# Concentrator_and_Cell_Modem_Headers.net
KiCad netlist of a schematic drawn in Altium Designer
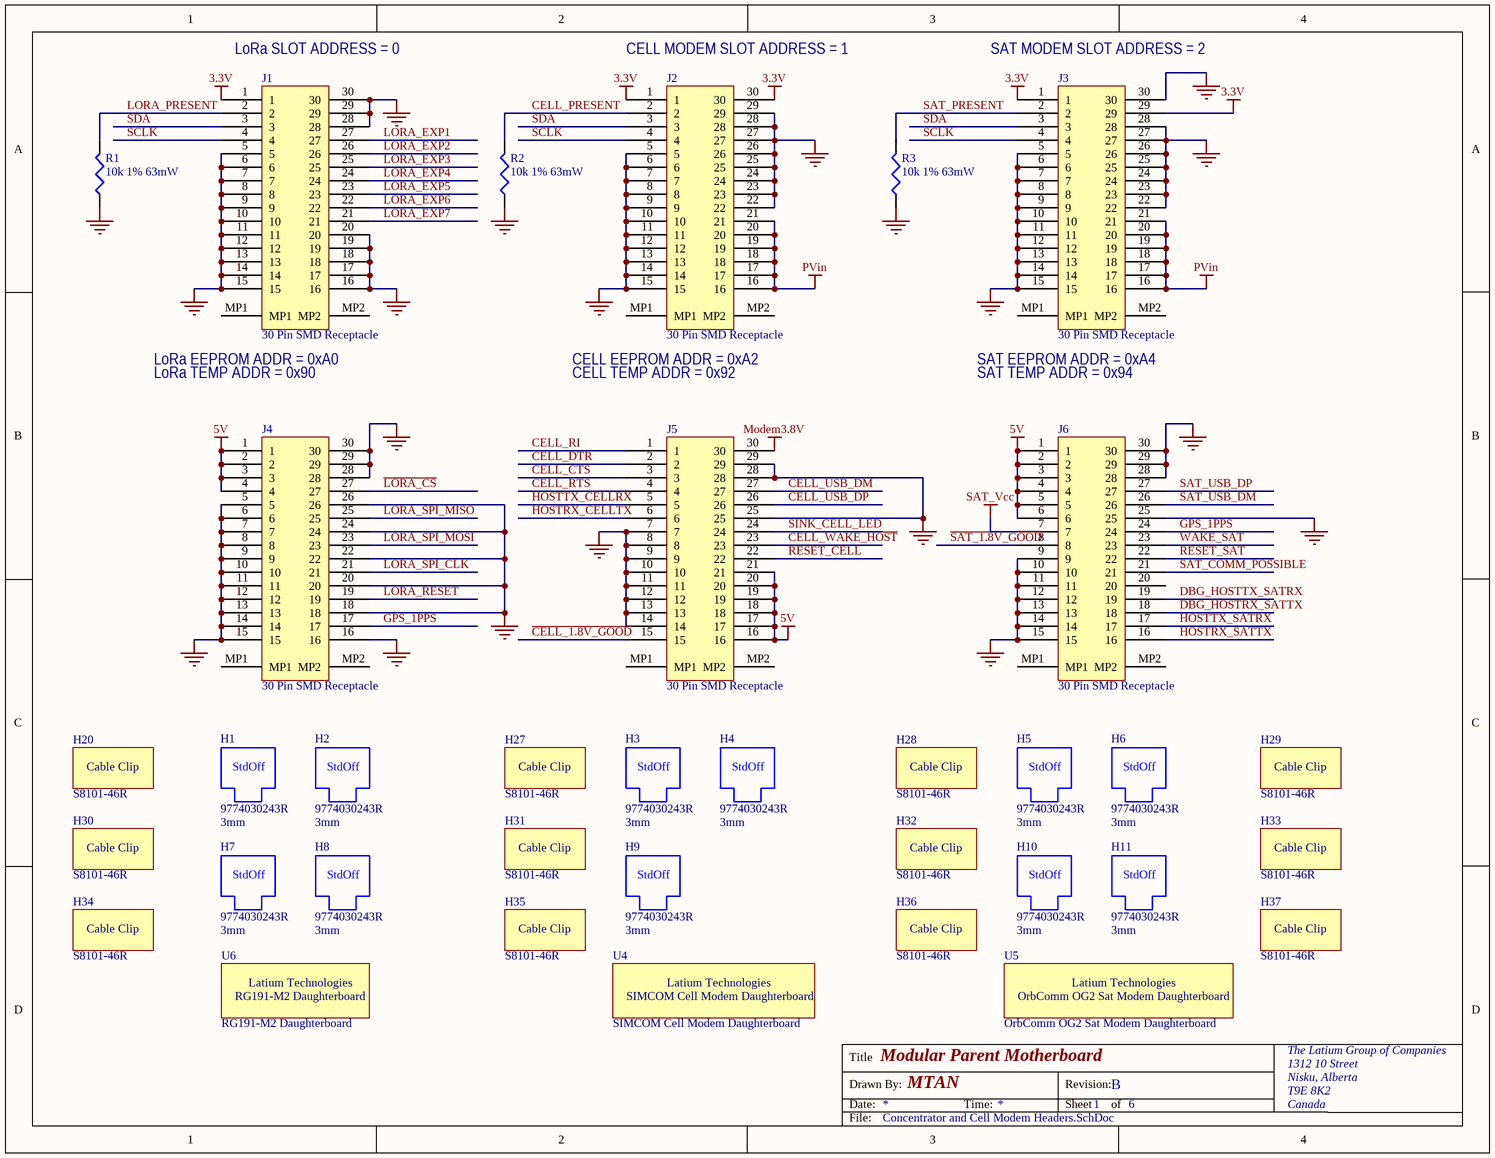
[diagram p0: Concentrator and Cell Modem Headers.SchDoc]

(export (version "E")
  (design (tool "Eeschema 10.0.6"))
  (components
    (comp (ref "H1")
      (value "9774030243R")
      (footprint "Wurth 9774030243R")
      (description "ROUND STANDOFF M2X0.4 STEEL 3MM")
      (fields (field (name "MANUFACTURER") "Wurth Electronics Inc") (field (name "HEIGHT") "3mm"))
      (libsource (lib "Latium Component Library") (part "SMD M3 Spacer"))
    )
    (comp (ref "H2")
      (value "9774030243R")
      (footprint "Wurth 9774030243R")
      (description "ROUND STANDOFF M2X0.4 STEEL 3MM")
      (fields (field (name "MANUFACTURER") "Wurth Electronics Inc") (field (name "HEIGHT") "3mm"))
      (libsource (lib "Latium Component Library") (part "SMD M3 Spacer"))
    )
    (comp (ref "H3")
      (value "9774030243R")
      (footprint "Wurth 9774030243R")
      (description "ROUND STANDOFF M2X0.4 STEEL 3MM")
      (fields (field (name "MANUFACTURER") "Wurth Electronics Inc") (field (name "HEIGHT") "3mm"))
      (libsource (lib "Latium Component Library") (part "SMD M3 Spacer"))
    )
    (comp (ref "H4")
      (value "9774030243R")
      (footprint "Wurth 9774030243R")
      (description "ROUND STANDOFF M2X0.4 STEEL 3MM")
      (fields (field (name "MANUFACTURER") "Wurth Electronics Inc") (field (name "HEIGHT") "3mm"))
      (libsource (lib "Latium Component Library") (part "SMD M3 Spacer"))
    )
    (comp (ref "H5")
      (value "9774030243R")
      (footprint "Wurth 9774030243R")
      (description "ROUND STANDOFF M2X0.4 STEEL 3MM")
      (fields (field (name "MANUFACTURER") "Wurth Electronics Inc") (field (name "HEIGHT") "3mm"))
      (libsource (lib "Latium Component Library") (part "SMD M3 Spacer"))
    )
    (comp (ref "H6")
      (value "9774030243R")
      (footprint "Wurth 9774030243R")
      (description "ROUND STANDOFF M2X0.4 STEEL 3MM")
      (fields (field (name "MANUFACTURER") "Wurth Electronics Inc") (field (name "HEIGHT") "3mm"))
      (libsource (lib "Latium Component Library") (part "SMD M3 Spacer"))
    )
    (comp (ref "H7")
      (value "9774030243R")
      (footprint "Wurth 9774030243R")
      (description "ROUND STANDOFF M2X0.4 STEEL 3MM")
      (fields (field (name "MANUFACTURER") "Wurth Electronics Inc") (field (name "HEIGHT") "3mm"))
      (libsource (lib "Latium Component Library") (part "SMD M3 Spacer"))
    )
    (comp (ref "H8")
      (value "9774030243R")
      (footprint "Wurth 9774030243R")
      (description "ROUND STANDOFF M2X0.4 STEEL 3MM")
      (fields (field (name "MANUFACTURER") "Wurth Electronics Inc") (field (name "HEIGHT") "3mm"))
      (libsource (lib "Latium Component Library") (part "SMD M3 Spacer"))
    )
    (comp (ref "H9")
      (value "9774030243R")
      (footprint "Wurth 9774030243R")
      (description "ROUND STANDOFF M2X0.4 STEEL 3MM")
      (fields (field (name "MANUFACTURER") "Wurth Electronics Inc") (field (name "HEIGHT") "3mm"))
      (libsource (lib "Latium Component Library") (part "SMD M3 Spacer"))
    )
    (comp (ref "H10")
      (value "9774030243R")
      (footprint "Wurth 9774030243R")
      (description "ROUND STANDOFF M2X0.4 STEEL 3MM")
      (fields (field (name "MANUFACTURER") "Wurth Electronics Inc") (field (name "HEIGHT") "3mm"))
      (libsource (lib "Latium Component Library") (part "SMD M3 Spacer"))
    )
    (comp (ref "H11")
      (value "9774030243R")
      (footprint "Wurth 9774030243R")
      (description "ROUND STANDOFF M2X0.4 STEEL 3MM")
      (fields (field (name "MANUFACTURER") "Wurth Electronics Inc") (field (name "HEIGHT") "3mm"))
      (libsource (lib "Latium Component Library") (part "SMD M3 Spacer"))
    )
    (comp (ref "H20")
      (value "S8101-46R")
      (footprint "Coax Cable Clip")
      (description "CBL CLIP C-TYPE SILVER SOLDER")
      (fields (field (name "MANUFACTURER") "Harwin Inc"))
      (libsource (lib "Latium Component Library") (part "Cable Clip"))
    )
    (comp (ref "H27")
      (value "S8101-46R")
      (footprint "Coax Cable Clip")
      (description "CBL CLIP C-TYPE SILVER SOLDER")
      (fields (field (name "MANUFACTURER") "Harwin Inc"))
      (libsource (lib "Latium Component Library") (part "Cable Clip"))
    )
    (comp (ref "H28")
      (value "S8101-46R")
      (footprint "Coax Cable Clip")
      (description "CBL CLIP C-TYPE SILVER SOLDER")
      (fields (field (name "MANUFACTURER") "Harwin Inc"))
      (libsource (lib "Latium Component Library") (part "Cable Clip"))
    )
    (comp (ref "H29")
      (value "S8101-46R")
      (footprint "Coax Cable Clip")
      (description "CBL CLIP C-TYPE SILVER SOLDER")
      (fields (field (name "MANUFACTURER") "Harwin Inc"))
      (libsource (lib "Latium Component Library") (part "Cable Clip"))
    )
    (comp (ref "H30")
      (value "S8101-46R")
      (footprint "Coax Cable Clip")
      (description "CBL CLIP C-TYPE SILVER SOLDER")
      (fields (field (name "MANUFACTURER") "Harwin Inc"))
      (libsource (lib "Latium Component Library") (part "Cable Clip"))
    )
    (comp (ref "H31")
      (value "S8101-46R")
      (footprint "Coax Cable Clip")
      (description "CBL CLIP C-TYPE SILVER SOLDER")
      (fields (field (name "MANUFACTURER") "Harwin Inc"))
      (libsource (lib "Latium Component Library") (part "Cable Clip"))
    )
    (comp (ref "H32")
      (value "S8101-46R")
      (footprint "Coax Cable Clip")
      (description "CBL CLIP C-TYPE SILVER SOLDER")
      (fields (field (name "MANUFACTURER") "Harwin Inc"))
      (libsource (lib "Latium Component Library") (part "Cable Clip"))
    )
    (comp (ref "H33")
      (value "S8101-46R")
      (footprint "Coax Cable Clip")
      (description "CBL CLIP C-TYPE SILVER SOLDER")
      (fields (field (name "MANUFACTURER") "Harwin Inc"))
      (libsource (lib "Latium Component Library") (part "Cable Clip"))
    )
    (comp (ref "H34")
      (value "S8101-46R")
      (footprint "Coax Cable Clip")
      (description "CBL CLIP C-TYPE SILVER SOLDER")
      (fields (field (name "MANUFACTURER") "Harwin Inc"))
      (libsource (lib "Latium Component Library") (part "Cable Clip"))
    )
    (comp (ref "H35")
      (value "S8101-46R")
      (footprint "Coax Cable Clip")
      (description "CBL CLIP C-TYPE SILVER SOLDER")
      (fields (field (name "MANUFACTURER") "Harwin Inc"))
      (libsource (lib "Latium Component Library") (part "Cable Clip"))
    )
    (comp (ref "H36")
      (value "S8101-46R")
      (footprint "Coax Cable Clip")
      (description "CBL CLIP C-TYPE SILVER SOLDER")
      (fields (field (name "MANUFACTURER") "Harwin Inc"))
      (libsource (lib "Latium Component Library") (part "Cable Clip"))
    )
    (comp (ref "H37")
      (value "S8101-46R")
      (footprint "Coax Cable Clip")
      (description "CBL CLIP C-TYPE SILVER SOLDER")
      (fields (field (name "MANUFACTURER") "Harwin Inc"))
      (libsource (lib "Latium Component Library") (part "Cable Clip"))
    )
    (comp (ref "J1")
      (value "30 Pin SMD Receptacle")
      (footprint "10132798-031100LF")
      (description "CONN RCPT 30POS SMD GOLD")
      (fields
        (field (name "MANUFACTURER") "Amphenol ICC (FCI)")
        (field (name "MANUFACTURER PART NUMBER") "10132798-031100LF")
      )
      (libsource (lib "Latium Component Library") (part "Amphenol 30 Pos BergStak Plug"))
    )
    (comp (ref "J2")
      (value "30 Pin SMD Receptacle")
      (footprint "10132798-031100LF")
      (description "CONN RCPT 30POS SMD GOLD")
      (fields
        (field (name "MANUFACTURER") "Amphenol ICC (FCI)")
        (field (name "MANUFACTURER PART NUMBER") "10132798-031100LF")
      )
      (libsource (lib "Latium Component Library") (part "Amphenol 30 Pos BergStak Plug"))
    )
    (comp (ref "J3")
      (value "30 Pin SMD Receptacle")
      (footprint "10132798-031100LF")
      (description "CONN RCPT 30POS SMD GOLD")
      (fields
        (field (name "MANUFACTURER") "Amphenol ICC (FCI)")
        (field (name "MANUFACTURER PART NUMBER") "10132798-031100LF")
      )
      (libsource (lib "Latium Component Library") (part "Amphenol 30 Pos BergStak Plug"))
    )
    (comp (ref "J4")
      (value "30 Pin SMD Receptacle")
      (footprint "10132798-031100LF")
      (description "CONN RCPT 30POS SMD GOLD")
      (fields
        (field (name "MANUFACTURER") "Amphenol ICC (FCI)")
        (field (name "MANUFACTURER PART NUMBER") "10132798-031100LF")
      )
      (libsource (lib "Latium Component Library") (part "Amphenol 30 Pos BergStak Plug"))
    )
    (comp (ref "J5")
      (value "30 Pin SMD Receptacle")
      (footprint "10132798-031100LF")
      (description "CONN RCPT 30POS SMD GOLD")
      (fields
        (field (name "MANUFACTURER") "Amphenol ICC (FCI)")
        (field (name "MANUFACTURER PART NUMBER") "10132798-031100LF")
      )
      (libsource (lib "Latium Component Library") (part "Amphenol 30 Pos BergStak Plug"))
    )
    (comp (ref "J6")
      (value "30 Pin SMD Receptacle")
      (footprint "10132798-031100LF")
      (description "CONN RCPT 30POS SMD GOLD")
      (fields
        (field (name "MANUFACTURER") "Amphenol ICC (FCI)")
        (field (name "MANUFACTURER PART NUMBER") "10132798-031100LF")
      )
      (libsource (lib "Latium Component Library") (part "Amphenol 30 Pos BergStak Plug"))
    )
    (comp (ref "R1")
      (value "10k 1% 63mW")
      (footprint "RESC1005L")
      (description "Resistor")
      (libsource (lib "Miscellaneous Devices") (part "Res3"))
    )
    (comp (ref "R2")
      (value "10k 1% 63mW")
      (footprint "RESC1005L")
      (description "Resistor")
      (libsource (lib "Miscellaneous Devices") (part "Res3"))
    )
    (comp (ref "R3")
      (value "10k 1% 63mW")
      (footprint "RESC1005L")
      (description "Resistor")
      (libsource (lib "Miscellaneous Devices") (part "Res3"))
    )
    (comp (ref "U4")
      (value "SIMCOM Cell Modem Daughterboard")
      (footprint "SIMCOM Cell Modem Daughterboard")
      (libsource (lib "Latium Component Library") (part "SIMCOM Cell Modem Daughterboard"))
    )
    (comp (ref "U5")
      (value "OrbComm OG2 Sat Modem Daughterboard")
      (footprint "OrbComm OG2 Daughterboard")
      (libsource (lib "Latium Component Library") (part "OrbComm OG2 Sat Modem Daughterboard"))
    )
    (comp (ref "U6")
      (value "RG191-M2 Daughterboard")
      (footprint "RG191-M2 LoRa Daughterboard")
      (libsource (lib "Latium Component Library") (part "RG191-M2 Daughterboard"))
    )
  )
  (nets
    (net (code "1") (name "/CELL_CTS") (class "Default")
      (node (ref "J5") (pin "3") (pinfunction "3_3") (pintype "passive"))
    )
    (net (code "2") (name "/CELL_DTR") (class "Default")
      (node (ref "J5") (pin "2") (pinfunction "2_2") (pintype "passive"))
    )
    (net (code "3") (name "/CELL_PRESENT") (class "Default")
      (node (ref "J2") (pin "2") (pinfunction "2_2") (pintype "passive"))
      (node (ref "R2") (pin "2") (pinfunction "2_2") (pintype "passive"))
    )
    (net (code "4") (name "/CELL_RI") (class "Default")
      (node (ref "J5") (pin "1") (pinfunction "1_1") (pintype "passive"))
    )
    (net (code "5") (name "/CELL_RTS") (class "Default")
      (node (ref "J5") (pin "4") (pinfunction "4_4") (pintype "passive"))
    )
    (net (code "6") (name "/CELL_USB_DM") (class "Default")
      (node (ref "J5") (pin "27") (pinfunction "27_27") (pintype "passive"))
    )
    (net (code "7") (name "/CELL_USB_DP") (class "Default")
      (node (ref "J5") (pin "26") (pinfunction "26_26") (pintype "passive"))
    )
    (net (code "8") (name "/DBG_HOSTRX_SATTX") (class "Default")
      (node (ref "J6") (pin "18") (pinfunction "18_18") (pintype "passive"))
    )
    (net (code "9") (name "/DBG_HOSTTX_SATRX") (class "Default")
      (node (ref "J6") (pin "19") (pinfunction "19_19") (pintype "passive"))
    )
    (net (code "10") (name "/GPS_1PPS") (class "Default")
      (node (ref "J4") (pin "17") (pinfunction "17_17") (pintype "passive"))
      (node (ref "J6") (pin "24") (pinfunction "24_24") (pintype "passive"))
    )
    (net (code "11") (name "/HOSTRX_CELLTX") (class "Default")
      (node (ref "J5") (pin "6") (pinfunction "6_6") (pintype "passive"))
    )
    (net (code "12") (name "/HOSTRX_SATTX") (class "Default")
      (node (ref "J6") (pin "16") (pinfunction "16_16") (pintype "passive"))
    )
    (net (code "13") (name "/HOSTTX_CELLRX") (class "Default")
      (node (ref "J5") (pin "5") (pinfunction "5_5") (pintype "passive"))
    )
    (net (code "14") (name "/HOSTTX_SATRX") (class "Default")
      (node (ref "J6") (pin "17") (pinfunction "17_17") (pintype "passive"))
    )
    (net (code "15") (name "/LORA_EXP1") (class "Default")
      (node (ref "J1") (pin "27") (pinfunction "27_27") (pintype "passive"))
    )
    (net (code "16") (name "/LORA_EXP2") (class "Default")
      (node (ref "J1") (pin "26") (pinfunction "26_26") (pintype "passive"))
    )
    (net (code "17") (name "/LORA_EXP3") (class "Default")
      (node (ref "J1") (pin "25") (pinfunction "25_25") (pintype "passive"))
    )
    (net (code "18") (name "/LORA_EXP4") (class "Default")
      (node (ref "J1") (pin "24") (pinfunction "24_24") (pintype "passive"))
    )
    (net (code "19") (name "/LORA_EXP5") (class "Default")
      (node (ref "J1") (pin "23") (pinfunction "23_23") (pintype "passive"))
    )
    (net (code "20") (name "/LORA_EXP6") (class "Default")
      (node (ref "J1") (pin "22") (pinfunction "22_22") (pintype "passive"))
    )
    (net (code "21") (name "/LORA_EXP7") (class "Default")
      (node (ref "J1") (pin "21") (pinfunction "21_21") (pintype "passive"))
    )
    (net (code "22") (name "/LORA_PRESENT") (class "Default")
      (node (ref "J1") (pin "2") (pinfunction "2_2") (pintype "passive"))
      (node (ref "R1") (pin "2") (pinfunction "2_2") (pintype "passive"))
    )
    (net (code "23") (name "/LORA_RESET") (class "Default")
      (node (ref "J4") (pin "19") (pinfunction "19_19") (pintype "passive"))
    )
    (net (code "24") (name "/LORA_SPI_CLK") (class "Default")
      (node (ref "J4") (pin "21") (pinfunction "21_21") (pintype "passive"))
    )
    (net (code "25") (name "/LORA_SPI_MISO") (class "Default")
      (node (ref "J4") (pin "25") (pinfunction "25_25") (pintype "passive"))
    )
    (net (code "26") (name "/LORA_SPI_MOSI") (class "Default")
      (node (ref "J4") (pin "23") (pinfunction "23_23") (pintype "passive"))
    )
    (net (code "27") (name "/RESET_CELL") (class "Default")
      (node (ref "J5") (pin "22") (pinfunction "22_22") (pintype "passive"))
    )
    (net (code "28") (name "/RESET_SAT") (class "Default")
      (node (ref "J6") (pin "22") (pinfunction "22_22") (pintype "passive"))
    )
    (net (code "29") (name "/SAT_COMM_POSSIBLE") (class "Default")
      (node (ref "J6") (pin "21") (pinfunction "21_21") (pintype "passive"))
    )
    (net (code "30") (name "/SAT_PRESENT") (class "Default")
      (node (ref "J3") (pin "2") (pinfunction "2_2") (pintype "passive"))
      (node (ref "R3") (pin "2") (pinfunction "2_2") (pintype "passive"))
    )
    (net (code "31") (name "/SAT_USB_DM") (class "Default")
      (node (ref "J6") (pin "26") (pinfunction "26_26") (pintype "passive"))
    )
    (net (code "32") (name "/SAT_USB_DP") (class "Default")
      (node (ref "J6") (pin "27") (pinfunction "27_27") (pintype "passive"))
    )
    (net (code "33") (name "/SCLK") (class "Default")
      (node (ref "J1") (pin "4") (pinfunction "4_4") (pintype "passive"))
      (node (ref "J2") (pin "4") (pinfunction "4_4") (pintype "passive"))
      (node (ref "J3") (pin "4") (pinfunction "4_4") (pintype "passive"))
    )
    (net (code "34") (name "/SDA") (class "Default")
      (node (ref "J1") (pin "3") (pinfunction "3_3") (pintype "passive"))
      (node (ref "J2") (pin "3") (pinfunction "3_3") (pintype "passive"))
      (node (ref "J3") (pin "3") (pinfunction "3_3") (pintype "passive"))
    )
    (net (code "35") (name "/WAKE_SAT") (class "Default")
      (node (ref "J6") (pin "23") (pinfunction "23_23") (pintype "passive"))
    )
    (net (code "36") (name "/~{CELL_1.8V_GOOD}") (class "Default")
      (node (ref "J5") (pin "15") (pinfunction "15_15") (pintype "passive"))
    )
    (net (code "37") (name "/~{CELL_WAKE_HOST}") (class "Default")
      (node (ref "J5") (pin "23") (pinfunction "23_23") (pintype "passive"))
    )
    (net (code "38") (name "/~{LORA_CS}") (class "Default")
      (node (ref "J4") (pin "27") (pinfunction "27_27") (pintype "passive"))
    )
    (net (code "39") (name "/~{SAT_1.8V_GOOD}") (class "Default")
      (node (ref "J6") (pin "8") (pinfunction "8_8") (pintype "passive"))
    )
    (net (code "40") (name "/~{SINK_CELL_LED}") (class "Default")
      (node (ref "J5") (pin "24") (pinfunction "24_24") (pintype "passive"))
    )
    (net (code "41") (name "3.3V") (class "Default")
      (node (ref "J1") (pin "1") (pinfunction "1_1") (pintype "passive"))
      (node (ref "J2") (pin "1") (pinfunction "1_1") (pintype "passive"))
      (node (ref "J2") (pin "30") (pinfunction "30_30") (pintype "passive"))
      (node (ref "J3") (pin "1") (pinfunction "1_1") (pintype "passive"))
      (node (ref "J3") (pin "29") (pinfunction "29_29") (pintype "passive"))
    )
    (net (code "42") (name "5V") (class "Default")
      (node (ref "J4") (pin "1") (pinfunction "1_1") (pintype "passive"))
      (node (ref "J4") (pin "2") (pinfunction "2_2") (pintype "passive"))
      (node (ref "J4") (pin "3") (pinfunction "3_3") (pintype "passive"))
      (node (ref "J4") (pin "4") (pinfunction "4_4") (pintype "passive"))
      (node (ref "J5") (pin "16") (pinfunction "16_16") (pintype "passive"))
      (node (ref "J5") (pin "17") (pinfunction "17_17") (pintype "passive"))
      (node (ref "J5") (pin "18") (pinfunction "18_18") (pintype "passive"))
      (node (ref "J5") (pin "19") (pinfunction "19_19") (pintype "passive"))
      (node (ref "J5") (pin "20") (pinfunction "20_20") (pintype "passive"))
      (node (ref "J5") (pin "21") (pinfunction "21_21") (pintype "passive"))
      (node (ref "J6") (pin "1") (pinfunction "1_1") (pintype "passive"))
      (node (ref "J6") (pin "2") (pinfunction "2_2") (pintype "passive"))
      (node (ref "J6") (pin "3") (pinfunction "3_3") (pintype "passive"))
      (node (ref "J6") (pin "4") (pinfunction "4_4") (pintype "passive"))
      (node (ref "J6") (pin "5") (pinfunction "5_5") (pintype "passive"))
      (node (ref "J6") (pin "6") (pinfunction "6_6") (pintype "passive"))
    )
    (net (code "43") (name "GND") (class "Default")
      (node (ref "J1") (pin "10") (pinfunction "10_10") (pintype "passive"))
      (node (ref "J1") (pin "11") (pinfunction "11_11") (pintype "passive"))
      (node (ref "J1") (pin "12") (pinfunction "12_12") (pintype "passive"))
      (node (ref "J1") (pin "13") (pinfunction "13_13") (pintype "passive"))
      (node (ref "J1") (pin "14") (pinfunction "14_14") (pintype "passive"))
      (node (ref "J1") (pin "15") (pinfunction "15_15") (pintype "passive"))
      (node (ref "J1") (pin "16") (pinfunction "16_16") (pintype "passive"))
      (node (ref "J1") (pin "17") (pinfunction "17_17") (pintype "passive"))
      (node (ref "J1") (pin "18") (pinfunction "18_18") (pintype "passive"))
      (node (ref "J1") (pin "19") (pinfunction "19_19") (pintype "passive"))
      (node (ref "J1") (pin "20") (pinfunction "20_20") (pintype "passive"))
      (node (ref "J1") (pin "28") (pinfunction "28_28") (pintype "passive"))
      (node (ref "J1") (pin "29") (pinfunction "29_29") (pintype "passive"))
      (node (ref "J1") (pin "30") (pinfunction "30_30") (pintype "passive"))
      (node (ref "J1") (pin "5") (pinfunction "5_5") (pintype "passive"))
      (node (ref "J1") (pin "6") (pinfunction "6_6") (pintype "passive"))
      (node (ref "J1") (pin "7") (pinfunction "7_7") (pintype "passive"))
      (node (ref "J1") (pin "8") (pinfunction "8_8") (pintype "passive"))
      (node (ref "J1") (pin "9") (pinfunction "9_9") (pintype "passive"))
      (node (ref "J2") (pin "10") (pinfunction "10_10") (pintype "passive"))
      (node (ref "J2") (pin "11") (pinfunction "11_11") (pintype "passive"))
      (node (ref "J2") (pin "12") (pinfunction "12_12") (pintype "passive"))
      (node (ref "J2") (pin "13") (pinfunction "13_13") (pintype "passive"))
      (node (ref "J2") (pin "14") (pinfunction "14_14") (pintype "passive"))
      (node (ref "J2") (pin "15") (pinfunction "15_15") (pintype "passive"))
      (node (ref "J2") (pin "22") (pinfunction "22_22") (pintype "passive"))
      (node (ref "J2") (pin "23") (pinfunction "23_23") (pintype "passive"))
      (node (ref "J2") (pin "24") (pinfunction "24_24") (pintype "passive"))
      (node (ref "J2") (pin "25") (pinfunction "25_25") (pintype "passive"))
      (node (ref "J2") (pin "26") (pinfunction "26_26") (pintype "passive"))
      (node (ref "J2") (pin "27") (pinfunction "27_27") (pintype "passive"))
      (node (ref "J2") (pin "28") (pinfunction "28_28") (pintype "passive"))
      (node (ref "J2") (pin "29") (pinfunction "29_29") (pintype "passive"))
      (node (ref "J2") (pin "5") (pinfunction "5_5") (pintype "passive"))
      (node (ref "J2") (pin "6") (pinfunction "6_6") (pintype "passive"))
      (node (ref "J2") (pin "7") (pinfunction "7_7") (pintype "passive"))
      (node (ref "J2") (pin "8") (pinfunction "8_8") (pintype "passive"))
      (node (ref "J2") (pin "9") (pinfunction "9_9") (pintype "passive"))
      (node (ref "J3") (pin "10") (pinfunction "10_10") (pintype "passive"))
      (node (ref "J3") (pin "11") (pinfunction "11_11") (pintype "passive"))
      (node (ref "J3") (pin "12") (pinfunction "12_12") (pintype "passive"))
      (node (ref "J3") (pin "13") (pinfunction "13_13") (pintype "passive"))
      (node (ref "J3") (pin "14") (pinfunction "14_14") (pintype "passive"))
      (node (ref "J3") (pin "15") (pinfunction "15_15") (pintype "passive"))
      (node (ref "J3") (pin "22") (pinfunction "22_22") (pintype "passive"))
      (node (ref "J3") (pin "23") (pinfunction "23_23") (pintype "passive"))
      (node (ref "J3") (pin "24") (pinfunction "24_24") (pintype "passive"))
      (node (ref "J3") (pin "25") (pinfunction "25_25") (pintype "passive"))
      (node (ref "J3") (pin "26") (pinfunction "26_26") (pintype "passive"))
      (node (ref "J3") (pin "27") (pinfunction "27_27") (pintype "passive"))
      (node (ref "J3") (pin "28") (pinfunction "28_28") (pintype "passive"))
      (node (ref "J3") (pin "30") (pinfunction "30_30") (pintype "passive"))
      (node (ref "J3") (pin "5") (pinfunction "5_5") (pintype "passive"))
      (node (ref "J3") (pin "6") (pinfunction "6_6") (pintype "passive"))
      (node (ref "J3") (pin "7") (pinfunction "7_7") (pintype "passive"))
      (node (ref "J3") (pin "8") (pinfunction "8_8") (pintype "passive"))
      (node (ref "J3") (pin "9") (pinfunction "9_9") (pintype "passive"))
      (node (ref "J4") (pin "10") (pinfunction "10_10") (pintype "passive"))
      (node (ref "J4") (pin "11") (pinfunction "11_11") (pintype "passive"))
      (node (ref "J4") (pin "12") (pinfunction "12_12") (pintype "passive"))
      (node (ref "J4") (pin "13") (pinfunction "13_13") (pintype "passive"))
      (node (ref "J4") (pin "14") (pinfunction "14_14") (pintype "passive"))
      (node (ref "J4") (pin "15") (pinfunction "15_15") (pintype "passive"))
      (node (ref "J4") (pin "16") (pinfunction "16_16") (pintype "passive"))
      (node (ref "J4") (pin "18") (pinfunction "18_18") (pintype "passive"))
      (node (ref "J4") (pin "20") (pinfunction "20_20") (pintype "passive"))
      (node (ref "J4") (pin "22") (pinfunction "22_22") (pintype "passive"))
      (node (ref "J4") (pin "24") (pinfunction "24_24") (pintype "passive"))
      (node (ref "J4") (pin "26") (pinfunction "26_26") (pintype "passive"))
      (node (ref "J4") (pin "28") (pinfunction "28_28") (pintype "passive"))
      (node (ref "J4") (pin "29") (pinfunction "29_29") (pintype "passive"))
      (node (ref "J4") (pin "30") (pinfunction "30_30") (pintype "passive"))
      (node (ref "J4") (pin "5") (pinfunction "5_5") (pintype "passive"))
      (node (ref "J4") (pin "6") (pinfunction "6_6") (pintype "passive"))
      (node (ref "J4") (pin "7") (pinfunction "7_7") (pintype "passive"))
      (node (ref "J4") (pin "8") (pinfunction "8_8") (pintype "passive"))
      (node (ref "J4") (pin "9") (pinfunction "9_9") (pintype "passive"))
      (node (ref "J5") (pin "10") (pinfunction "10_10") (pintype "passive"))
      (node (ref "J5") (pin "11") (pinfunction "11_11") (pintype "passive"))
      (node (ref "J5") (pin "12") (pinfunction "12_12") (pintype "passive"))
      (node (ref "J5") (pin "13") (pinfunction "13_13") (pintype "passive"))
      (node (ref "J5") (pin "14") (pinfunction "14_14") (pintype "passive"))
      (node (ref "J5") (pin "25") (pinfunction "25_25") (pintype "passive"))
      (node (ref "J5") (pin "28") (pinfunction "28_28") (pintype "passive"))
      (node (ref "J5") (pin "29") (pinfunction "29_29") (pintype "passive"))
      (node (ref "J5") (pin "7") (pinfunction "7_7") (pintype "passive"))
      (node (ref "J5") (pin "8") (pinfunction "8_8") (pintype "passive"))
      (node (ref "J5") (pin "9") (pinfunction "9_9") (pintype "passive"))
      (node (ref "J6") (pin "10") (pinfunction "10_10") (pintype "passive"))
      (node (ref "J6") (pin "11") (pinfunction "11_11") (pintype "passive"))
      (node (ref "J6") (pin "12") (pinfunction "12_12") (pintype "passive"))
      (node (ref "J6") (pin "13") (pinfunction "13_13") (pintype "passive"))
      (node (ref "J6") (pin "14") (pinfunction "14_14") (pintype "passive"))
      (node (ref "J6") (pin "15") (pinfunction "15_15") (pintype "passive"))
      (node (ref "J6") (pin "25") (pinfunction "25_25") (pintype "passive"))
      (node (ref "J6") (pin "28") (pinfunction "28_28") (pintype "passive"))
      (node (ref "J6") (pin "29") (pinfunction "29_29") (pintype "passive"))
      (node (ref "J6") (pin "30") (pinfunction "30_30") (pintype "passive"))
      (node (ref "J6") (pin "9") (pinfunction "9_9") (pintype "passive"))
      (node (ref "R1") (pin "1") (pinfunction "1_1") (pintype "passive"))
      (node (ref "R2") (pin "1") (pinfunction "1_1") (pintype "passive"))
      (node (ref "R3") (pin "1") (pinfunction "1_1") (pintype "passive"))
    )
    (net (code "44") (name "Modem3.8V") (class "Default")
      (node (ref "J5") (pin "30") (pinfunction "30_30") (pintype "passive"))
    )
    (net (code "45") (name "PVin") (class "Default")
      (node (ref "J2") (pin "16") (pinfunction "16_16") (pintype "passive"))
      (node (ref "J2") (pin "17") (pinfunction "17_17") (pintype "passive"))
      (node (ref "J2") (pin "18") (pinfunction "18_18") (pintype "passive"))
      (node (ref "J2") (pin "19") (pinfunction "19_19") (pintype "passive"))
      (node (ref "J2") (pin "20") (pinfunction "20_20") (pintype "passive"))
      (node (ref "J2") (pin "21") (pinfunction "21_21") (pintype "passive"))
      (node (ref "J3") (pin "16") (pinfunction "16_16") (pintype "passive"))
      (node (ref "J3") (pin "17") (pinfunction "17_17") (pintype "passive"))
      (node (ref "J3") (pin "18") (pinfunction "18_18") (pintype "passive"))
      (node (ref "J3") (pin "19") (pinfunction "19_19") (pintype "passive"))
      (node (ref "J3") (pin "20") (pinfunction "20_20") (pintype "passive"))
      (node (ref "J3") (pin "21") (pinfunction "21_21") (pintype "passive"))
    )
    (net (code "46") (name "SAT_Vcc") (class "Default")
      (node (ref "J6") (pin "7") (pinfunction "7_7") (pintype "passive"))
    )
    (net (code "47") (name "unconnected-(J1-PadMP1)") (class "Default")
      (node (ref "J1") (pin "MP1") (pinfunction "MP1_MP1") (pintype "passive"))
    )
    (net (code "48") (name "unconnected-(J1-PadMP2)") (class "Default")
      (node (ref "J1") (pin "MP2") (pinfunction "MP2_MP2") (pintype "passive"))
    )
    (net (code "49") (name "unconnected-(J2-PadMP1)") (class "Default")
      (node (ref "J2") (pin "MP1") (pinfunction "MP1_MP1") (pintype "passive"))
    )
    (net (code "50") (name "unconnected-(J2-PadMP2)") (class "Default")
      (node (ref "J2") (pin "MP2") (pinfunction "MP2_MP2") (pintype "passive"))
    )
    (net (code "51") (name "unconnected-(J3-PadMP1)") (class "Default")
      (node (ref "J3") (pin "MP1") (pinfunction "MP1_MP1") (pintype "passive"))
    )
    (net (code "52") (name "unconnected-(J3-PadMP2)") (class "Default")
      (node (ref "J3") (pin "MP2") (pinfunction "MP2_MP2") (pintype "passive"))
    )
    (net (code "53") (name "unconnected-(J4-PadMP1)") (class "Default")
      (node (ref "J4") (pin "MP1") (pinfunction "MP1_MP1") (pintype "passive"))
    )
    (net (code "54") (name "unconnected-(J4-PadMP2)") (class "Default")
      (node (ref "J4") (pin "MP2") (pinfunction "MP2_MP2") (pintype "passive"))
    )
    (net (code "55") (name "unconnected-(J5-PadMP1)") (class "Default")
      (node (ref "J5") (pin "MP1") (pinfunction "MP1_MP1") (pintype "passive"))
    )
    (net (code "56") (name "unconnected-(J5-PadMP2)") (class "Default")
      (node (ref "J5") (pin "MP2") (pinfunction "MP2_MP2") (pintype "passive"))
    )
    (net (code "57") (name "unconnected-(J6-Pad20)") (class "Default")
      (node (ref "J6") (pin "20") (pinfunction "20_20") (pintype "passive"))
    )
    (net (code "58") (name "unconnected-(J6-PadMP1)") (class "Default")
      (node (ref "J6") (pin "MP1") (pinfunction "MP1_MP1") (pintype "passive"))
    )
    (net (code "59") (name "unconnected-(J6-PadMP2)") (class "Default")
      (node (ref "J6") (pin "MP2") (pinfunction "MP2_MP2") (pintype "passive"))
    )
  )
)
